# Schematic.net
KiCad netlist of a schematic drawn in Altium Designer
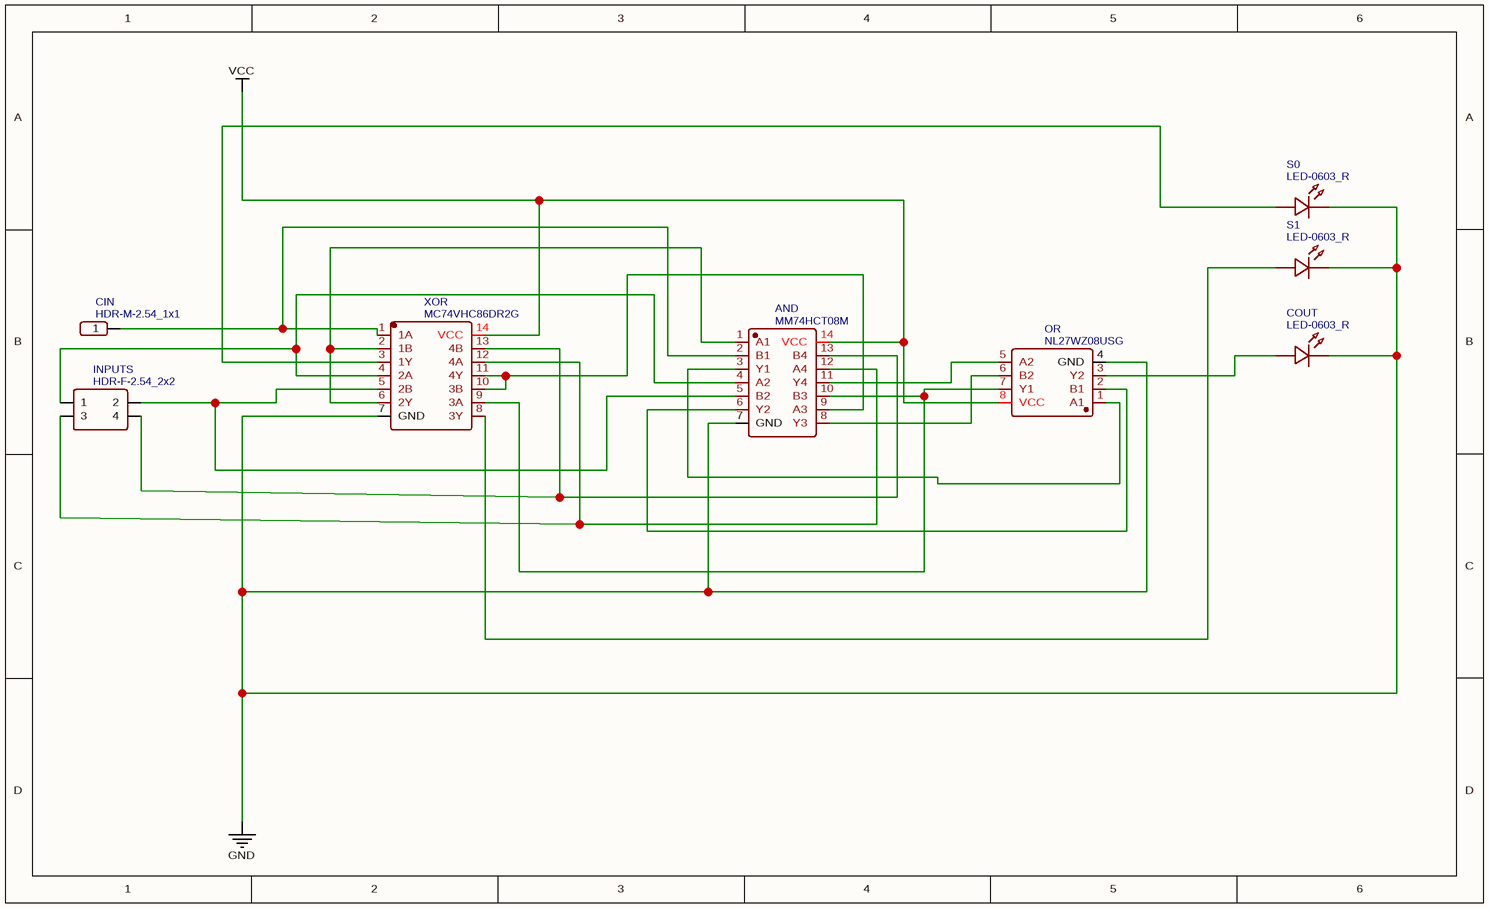
[diagram p0: Schematic.schdoc]

(export (version "E")
  (design (tool "Eeschema 10.0.6"))
  (components
    (comp (ref "AND")
      (value "MM74HCT08M")
      (fields (field (name "BOM_SUPPLIER PART") "C900098") (field (name "CONTRIBUTOR") "LCSC"))
      (libsource (lib "altium-import") (part "root_0_MM74HCT08M_"))
    )
    (comp (ref "CIN")
      (value "HDR-M-2.54_1x1")
      (fields (field (name "BOM_SUPPLIER PART") "C81276") (field (name "CONTRIBUTOR") "LCEDA_Lib"))
      (libsource (lib "altium-import") (part "root_2_HDR-M-2.54_1x1_"))
    )
    (comp (ref "COUT")
      (value "LED-0603_R")
      (fields
        (field (name "BOM_MANUFACTURER PART") "19-217/R6C-AL1M2VY/3T")
        (field (name "BOM_SUPPLIER PART") "C72044")
        (field (name "CONTRIBUTOR") "LCEDA_01")
      )
      (libsource (lib "altium-import") (part "root_0_LED-0603_R_"))
    )
    (comp (ref "INPUTS")
      (value "HDR-F-2.54_2x2")
      (fields (field (name "BOM_SUPPLIER PART") "C239342") (field (name "CONTRIBUTOR") "LCEDA_Lib"))
      (libsource (lib "altium-import") (part "root_0_HDR-F-2.54_2x2_"))
    )
    (comp (ref "OR")
      (value "NL27WZ08USG")
      (fields (field (name "BOM_SUPPLIER PART") "C209702") (field (name "CONTRIBUTOR") "LCSC"))
      (libsource (lib "altium-import") (part "root_1_NL27WZ08USG_"))
    )
    (comp (ref "S0")
      (value "LED-0603_R")
      (fields
        (field (name "BOM_MANUFACTURER PART") "19-217/R6C-AL1M2VY/3T")
        (field (name "BOM_SUPPLIER PART") "C72044")
        (field (name "CONTRIBUTOR") "LCEDA_01")
      )
      (libsource (lib "altium-import") (part "root_0_LED-0603_R_"))
    )
    (comp (ref "S1")
      (value "LED-0603_R")
      (fields
        (field (name "BOM_MANUFACTURER PART") "19-217/R6C-AL1M2VY/3T")
        (field (name "BOM_SUPPLIER PART") "C72044")
        (field (name "CONTRIBUTOR") "LCEDA_01")
      )
      (libsource (lib "altium-import") (part "root_0_LED-0603_R_"))
    )
    (comp (ref "XOR")
      (value "MC74VHC86DR2G")
      (fields (field (name "BOM_SUPPLIER PART") "C233551") (field (name "CONTRIBUTOR") "LCSC"))
      (libsource (lib "altium-import") (part "root_0_MC74VHC86DR2G_"))
    )
  )
  (nets
    (net (code "1") (name "GND") (class "Default")
      (node (ref "AND") (pin "7") (pinfunction "GND_7") (pintype "passive"))
      (node (ref "COUT") (pin "2") (pinfunction "2_2") (pintype "passive"))
      (node (ref "OR") (pin "4") (pinfunction "GND_4") (pintype "passive"))
      (node (ref "S0") (pin "2") (pinfunction "2_2") (pintype "passive"))
      (node (ref "S1") (pin "2") (pinfunction "2_2") (pintype "passive"))
      (node (ref "XOR") (pin "7") (pinfunction "GND_7") (pintype "passive"))
    )
    (net (code "2") (name "Net-(AND-A1)") (class "Default")
      (node (ref "AND") (pin "1") (pinfunction "A1_1") (pintype "passive"))
      (node (ref "XOR") (pin "2") (pinfunction "1B_2") (pintype "passive"))
      (node (ref "XOR") (pin "6") (pinfunction "2Y_6") (pintype "passive"))
    )
    (net (code "3") (name "Net-(AND-A2)") (class "Default")
      (node (ref "AND") (pin "4") (pinfunction "A2_4") (pintype "passive"))
      (node (ref "INPUTS") (pin "1") (pinfunction "1_1") (pintype "passive"))
      (node (ref "XOR") (pin "4") (pinfunction "2A_4") (pintype "passive"))
    )
    (net (code "4") (name "Net-(AND-A3)") (class "Default")
      (node (ref "AND") (pin "9") (pinfunction "A3_9") (pintype "passive"))
      (node (ref "XOR") (pin "10") (pinfunction "3B_10") (pintype "passive"))
      (node (ref "XOR") (pin "11") (pinfunction "4Y_11") (pintype "passive"))
    )
    (net (code "5") (name "Net-(AND-A4)") (class "Default")
      (node (ref "AND") (pin "12") (pinfunction "A4_12") (pintype "passive"))
      (node (ref "INPUTS") (pin "3") (pinfunction "3_3") (pintype "passive"))
      (node (ref "XOR") (pin "12") (pinfunction "4A_12") (pintype "passive"))
    )
    (net (code "6") (name "Net-(AND-B1)") (class "Default")
      (node (ref "AND") (pin "2") (pinfunction "B1_2") (pintype "passive"))
      (node (ref "CIN") (pin "1") (pinfunction "1_1") (pintype "passive"))
      (node (ref "XOR") (pin "1") (pinfunction "1A_1") (pintype "passive"))
    )
    (net (code "7") (name "Net-(AND-B2)") (class "Default")
      (node (ref "AND") (pin "5") (pinfunction "B2_5") (pintype "passive"))
      (node (ref "INPUTS") (pin "2") (pinfunction "2_2") (pintype "passive"))
      (node (ref "XOR") (pin "5") (pinfunction "2B_5") (pintype "passive"))
    )
    (net (code "8") (name "Net-(AND-B3)") (class "Default")
      (node (ref "AND") (pin "10") (pinfunction "B3_10") (pintype "passive"))
      (node (ref "OR") (pin "7") (pinfunction "Y1_7") (pintype "passive"))
      (node (ref "XOR") (pin "9") (pinfunction "3A_9") (pintype "passive"))
    )
    (net (code "9") (name "Net-(AND-B4)") (class "Default")
      (node (ref "AND") (pin "13") (pinfunction "B4_13") (pintype "passive"))
      (node (ref "INPUTS") (pin "4") (pinfunction "4_4") (pintype "passive"))
      (node (ref "XOR") (pin "13") (pinfunction "4B_13") (pintype "passive"))
    )
    (net (code "10") (name "Net-(AND-Y1)") (class "Default")
      (node (ref "AND") (pin "3") (pinfunction "Y1_3") (pintype "passive"))
      (node (ref "OR") (pin "1") (pinfunction "A1_1") (pintype "passive"))
    )
    (net (code "11") (name "Net-(AND-Y2)") (class "Default")
      (node (ref "AND") (pin "6") (pinfunction "Y2_6") (pintype "passive"))
      (node (ref "OR") (pin "2") (pinfunction "B1_2") (pintype "passive"))
    )
    (net (code "12") (name "Net-(AND-Y3)") (class "Default")
      (node (ref "AND") (pin "8") (pinfunction "Y3_8") (pintype "passive"))
      (node (ref "OR") (pin "6") (pinfunction "B2_6") (pintype "passive"))
    )
    (net (code "13") (name "Net-(AND-Y4)") (class "Default")
      (node (ref "AND") (pin "11") (pinfunction "Y4_11") (pintype "passive"))
      (node (ref "OR") (pin "5") (pinfunction "A2_5") (pintype "passive"))
    )
    (net (code "14") (name "Net-(OR-Y2)") (class "Default")
      (node (ref "COUT") (pin "1") (pinfunction "1_1") (pintype "passive"))
      (node (ref "OR") (pin "3") (pinfunction "Y2_3") (pintype "passive"))
    )
    (net (code "15") (name "Net-(XOR-1Y)") (class "Default")
      (node (ref "S0") (pin "1") (pinfunction "1_1") (pintype "passive"))
      (node (ref "XOR") (pin "3") (pinfunction "1Y_3") (pintype "passive"))
    )
    (net (code "16") (name "Net-(XOR-3Y)") (class "Default")
      (node (ref "S1") (pin "1") (pinfunction "1_1") (pintype "passive"))
      (node (ref "XOR") (pin "8") (pinfunction "3Y_8") (pintype "passive"))
    )
    (net (code "17") (name "VCC") (class "Default")
      (node (ref "AND") (pin "14") (pinfunction "VCC_14") (pintype "passive"))
      (node (ref "OR") (pin "8") (pinfunction "VCC_8") (pintype "passive"))
      (node (ref "XOR") (pin "14") (pinfunction "VCC_14") (pintype "passive"))
    )
  )
)
